# MAIN.net
KiCad netlist of a schematic drawn in Altium Designer
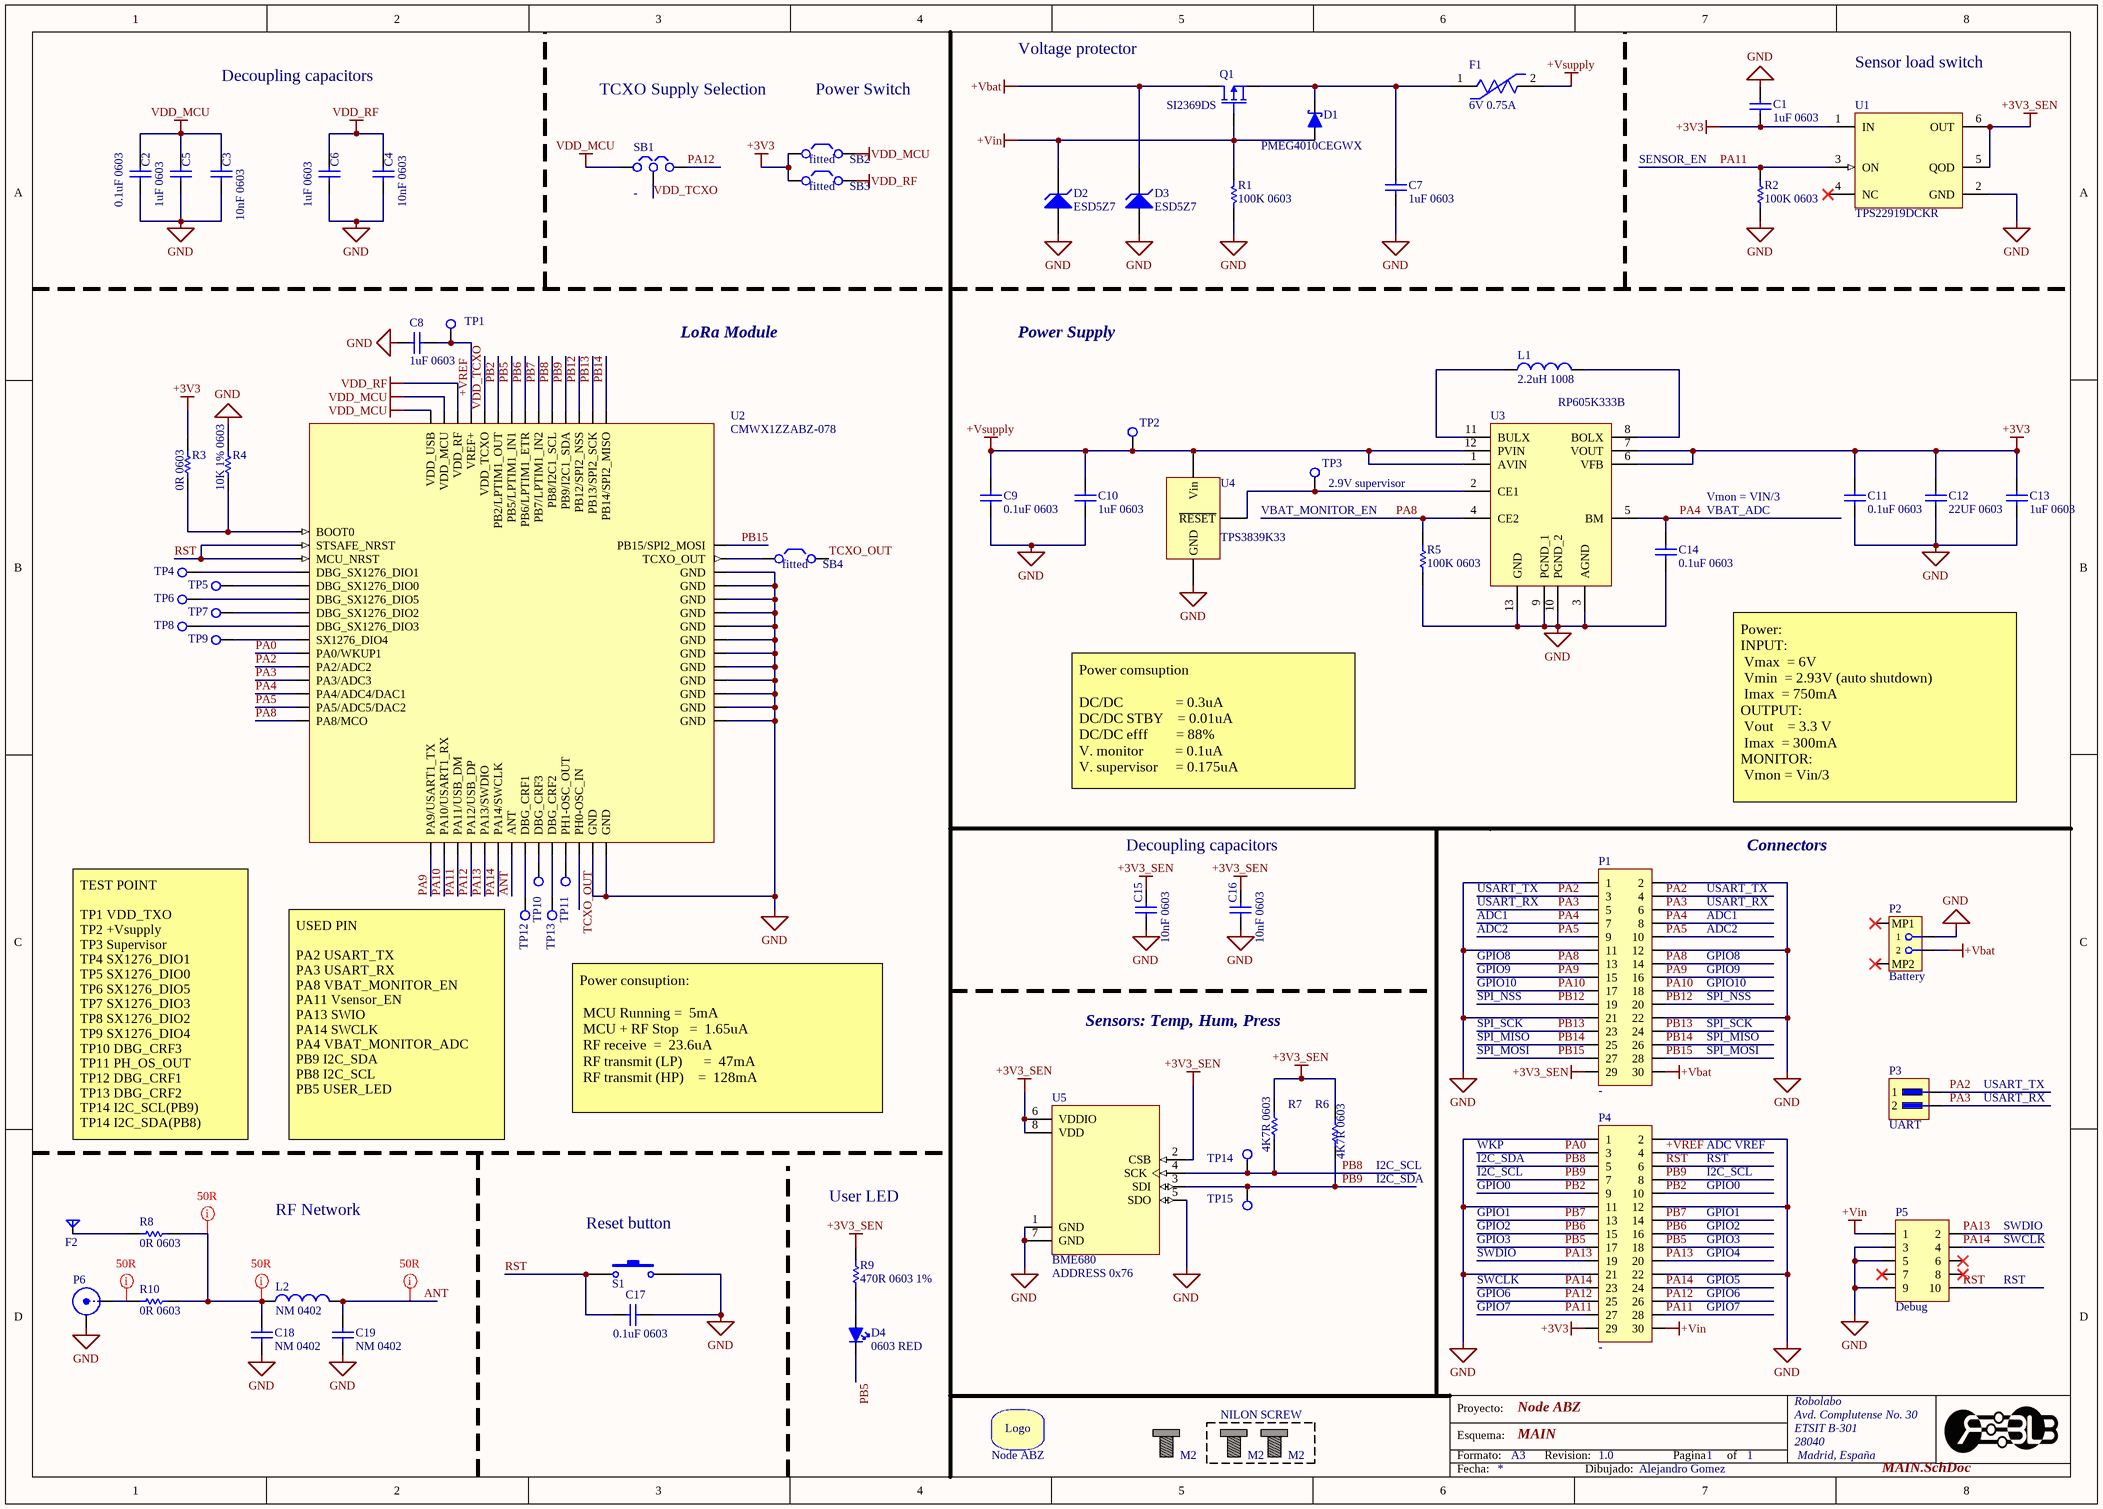
[diagram p0: MAIN.SchDoc]

(export (version "E")
  (design (tool "Eeschema 10.0.6"))
  (components
    (comp (ref "C1")
      (value "1uF 0603")
      (footprint "CAP_SMD_0603")
      (description "CAP CER, 1UF, 10V, X5R, 10%, 0603")
      (fields
        (field (name "MANUFACTURER") "KEMET")
        (field (name "MANUFACTURER PART NUMBER") "C0603C105K8PACTU")
      )
      (libsource (lib "Ceramic_Capacitor") (part "C0603C105K8PACTU"))
    )
    (comp (ref "C2")
      (value "0.1uF 0603")
      (footprint "CAP_SMD_0603")
      (description "Cap Ceramic 0.1uF 6.3V X7R 10% Pad SMD 0603 125°C T/R")
      (fields (field (name "TOLERANCE") "10%"))
      (libsource (lib "Ceramic_Capacitor") (part "C0603C104K9RACTU"))
    )
    (comp (ref "C3")
      (value "10nF 0603")
      (footprint "CAP_SMD_0603")
      (fields
        (field (name "TOLERANCE") "10%")
        (field (name "MANUFACTURER") "KEMET")
        (field (name "MANUFACTURER PART NUMBER") "C0603C103K5RACTU")
      )
      (libsource (lib "Ceramic_Capacitor") (part "C0603C103K5RACTU"))
    )
    (comp (ref "C4")
      (value "10nF 0603")
      (footprint "CAP_SMD_0603")
      (fields
        (field (name "TOLERANCE") "10%")
        (field (name "MANUFACTURER") "KEMET")
        (field (name "MANUFACTURER PART NUMBER") "C0603C103K5RACTU")
      )
      (libsource (lib "Ceramic_Capacitor") (part "C0603C103K5RACTU"))
    )
    (comp (ref "C5")
      (value "1uF 0603")
      (footprint "CAP_SMD_0603")
      (description "CAP CER, 1UF, 10V, X5R, 10%, 0603")
      (fields
        (field (name "MANUFACTURER") "KEMET")
        (field (name "MANUFACTURER PART NUMBER") "C0603C105K8PACTU")
      )
      (libsource (lib "Ceramic_Capacitor") (part "C0603C105K8PACTU"))
    )
    (comp (ref "C6")
      (value "1uF 0603")
      (footprint "CAP_SMD_0603")
      (description "CAP CER, 1UF, 10V, X5R, 10%, 0603")
      (fields
        (field (name "MANUFACTURER") "KEMET")
        (field (name "MANUFACTURER PART NUMBER") "C0603C105K8PACTU")
      )
      (libsource (lib "Ceramic_Capacitor") (part "C0603C105K8PACTU"))
    )
    (comp (ref "C7")
      (value "1uF 0603")
      (footprint "CAP_SMD_0603")
      (description "CAP CER, 1UF, 10V, X5R, 10%, 0603")
      (fields
        (field (name "MANUFACTURER") "KEMET")
        (field (name "MANUFACTURER PART NUMBER") "C0603C105K8PACTU")
      )
      (libsource (lib "Ceramic_Capacitor") (part "C0603C105K8PACTU"))
    )
    (comp (ref "C8")
      (value "1uF 0603")
      (footprint "CAP_SMD_0603")
      (description "CAP CER, 1UF, 10V, X5R, 10%, 0603")
      (fields
        (field (name "MANUFACTURER") "KEMET")
        (field (name "MANUFACTURER PART NUMBER") "C0603C105K8PACTU")
      )
      (libsource (lib "Ceramic_Capacitor") (part "C0603C105K8PACTU"))
    )
    (comp (ref "C9")
      (value "0.1uF 0603")
      (footprint "CAP_SMD_0603")
      (description "CAP CER, 0.1UF, 6.3V, X7R, 10%, 0603")
      (fields (field (name "TOLERANCE") "10%"))
      (libsource (lib "Ceramic_Capacitor") (part "C0603C104K9RACTU"))
    )
    (comp (ref "C10")
      (value "1uF 0603")
      (footprint "CAP_SMD_0603")
      (description "CAP CER, 1UF, 10V, X5R, 10%, 0603")
      (fields
        (field (name "MANUFACTURER") "KEMET")
        (field (name "MANUFACTURER PART NUMBER") "C0603C105K8PACTU")
      )
      (libsource (lib "Ceramic_Capacitor") (part "C0603C105K8PACTU"))
    )
    (comp (ref "C11")
      (value "0.1uF 0603")
      (footprint "CAP_SMD_0603")
      (description "CAP CER, 0.1UF, 6.3V, X7R, 10%, 0603")
      (fields (field (name "TOLERANCE") "10%"))
      (libsource (lib "Ceramic_Capacitor") (part "C0603C104K9RACTU"))
    )
    (comp (ref "C12")
      (value "22UF 0603")
      (footprint "CAP_SMD_0603")
      (description "CAP CER, 22UF, 100V, X8R, 2%, 0603")
      (fields
        (field (name "MANUFACTURER") "KEMET")
        (field (name "MANUFACTURER PART NUMBER") "C0603C300G1HACTU")
      )
      (libsource (lib "Ceramic_Capacitor") (part "C0603C300G1HACTU"))
    )
    (comp (ref "C13")
      (value "1uF 0603")
      (footprint "CAP_SMD_0603")
      (description "CAP CER, 1UF, 10V, X5R, 10%, 0603")
      (fields
        (field (name "MANUFACTURER") "KEMET")
        (field (name "MANUFACTURER PART NUMBER") "C0603C105K8PACTU")
      )
      (libsource (lib "Ceramic_Capacitor") (part "C0603C105K8PACTU"))
    )
    (comp (ref "C14")
      (value "0.1uF 0603")
      (footprint "CAP_SMD_0603")
      (description "CAP CER, 0.1UF, 6.3V, X7R, 10%, 0603")
      (fields (field (name "TOLERANCE") "10%"))
      (libsource (lib "Ceramic_Capacitor") (part "C0603C104K9RACTU"))
    )
    (comp (ref "C15")
      (value "10nF 0603")
      (footprint "CAP_SMD_0603")
      (fields
        (field (name "TOLERANCE") "10%")
        (field (name "MANUFACTURER") "KEMET")
        (field (name "MANUFACTURER PART NUMBER") "C0603C103K5RACTU")
      )
      (libsource (lib "Ceramic_Capacitor") (part "C0603C103K5RACTU"))
    )
    (comp (ref "C16")
      (value "10nF 0603")
      (footprint "CAP_SMD_0603")
      (fields
        (field (name "TOLERANCE") "10%")
        (field (name "MANUFACTURER") "KEMET")
        (field (name "MANUFACTURER PART NUMBER") "C0603C103K5RACTU")
      )
      (libsource (lib "Ceramic_Capacitor") (part "C0603C103K5RACTU"))
    )
    (comp (ref "C17")
      (value "0.1uF 0603")
      (footprint "CAP_SMD_0603")
      (description "Cap Ceramic 0.1uF 6.3V X7R 10% Pad SMD 0603 125°C T/R")
      (fields (field (name "TOLERANCE") "10%"))
      (libsource (lib "Ceramic_Capacitor") (part "C0603C104K9RACTU"))
    )
    (comp (ref "C18")
      (value "NM 0402")
      (footprint "CAP_SMD_0402")
      (description "NM")
      (fields (field (name "TOLERANCE") "10%"))
      (libsource (lib "Ceramic_Capacitor") (part "C0603C103K9RACTU"))
    )
    (comp (ref "C19")
      (value "NM 0402")
      (footprint "CAP_SMD_0402")
      (description "NM")
      (fields (field (name "TOLERANCE") "10%"))
      (libsource (lib "Ceramic_Capacitor") (part "C0603C103K9RACTU"))
    )
    (comp (ref "D1")
      (value "PMEG4010CEGWX")
      (footprint "SODFL358X130-2N")
      (description "DIODE SCHOTTKY 40V 1A 570mV SOD123")
      (fields (field (name "MANUFACTURER") "Nexperia"))
      (libsource (lib "schottky") (part "PMEG4010CEGWX"))
    )
    (comp (ref "D2")
      (value "ESD5Z7")
      (footprint "SODFL160X70-2N")
      (description "TVS Diodes / ESD Suppressors SOD523 ESD DIODE")
      (fields
        (field (name "MANUFACTURER") "ON Semiconductor")
        (field (name "MANUFACTURER PART NUMBER") "ESD5Z7.0T1G")
      )
      (libsource (lib "ESD") (part "ESD5Z7.0T1G"))
    )
    (comp (ref "D3")
      (value "ESD5Z7")
      (footprint "SODFL160X70-2N")
      (description "TVS Diodes / ESD Suppressors SOD523 ESD DIODE")
      (fields
        (field (name "MANUFACTURER") "ON Semiconductor")
        (field (name "MANUFACTURER PART NUMBER") "ESD5Z7.0T1G")
      )
      (libsource (lib "ESD") (part "ESD5Z7.0T1G"))
    )
    (comp (ref "D4")
      (value "0603 RED")
      (footprint "DIODE_LED_SMD_0603")
      (description "Led, Red, 65MCD, 631NM, SMD, 1608")
      (fields
        (field (name "MANUFACTURER") "Kingbright")
        (field (name "MANUFACTURER PART NUMBER") "KPG1-1608SURC-TT")
      )
      (libsource (lib "LED") (part "KPG1-1608SURC-TT"))
    )
    (comp (ref "F1")
      (value "6V 0.75A")
      (footprint "FP-0ZCK0075FF2E-MFG")
      (description "BEL FUSE - 0ZCK0075FF2E - FUSE, RESETTABLE PTC, 6VDC, 0.75A, SMD")
      (fields (field (name "MANUFACTURER") "Bel") (field (name "MANUFACTURER PART NUMBER") "0ZCK0075FF2E"))
      (libsource (lib "PPTC_Fuses") (part "0ZCK0075FF2E"))
    )
    (comp (ref "F2")
      (value "Helical 868-915Mhz")
      (footprint "Helical_868-915MHZ")
      (description "19x11mm Helical antenna. Requieres load matching  (impedance at 868MHz: 10-88j, VSWR 22)")
      (libsource (lib "antenna_pcb") (part "Helical_868-915MHZ"))
    )
    (comp (ref "L1")
      (value "2.2uH 1008")
      (footprint "IND_SMD_1008")
      (description "2.2uH, 1.3A , 20%, 1MHz")
      (fields
        (field (name "MANUFACTURER") "Bourns")
        (field (name "MANUFACTURER PART NUMBER") "CVH252009-2R2M")
      )
      (libsource (lib "Fixed_inductors") (part "CVH252009-2R2M"))
    )
    (comp (ref "L2")
      (value "NM 0402")
      (footprint "IND_SMD_0402")
      (description "NM")
      (fields
        (field (name "MANUFACTURER") "Fair-Rite")
        (field (name "MANUFACTURER PART NUMBER") "2506031217Z0")
      )
      (libsource (lib "Ferrite") (part "2506031217Z0"))
    )
    (comp (ref "logo1")
      (value "Node ABZ")
      (footprint "Robolabo10x25")
      (libsource (lib "logo") (part "Robolabo"))
    )
    (comp (ref "P1")
      (value "-")
      (footprint "CONN-2X15-1.27-MALE-RECT-SMD")
      (description "CONN-2X15-1.27-MALE-RECT")
      (libsource (lib "pin") (part "CONN-2X15-1.27-MALE-RECT"))
    )
    (comp (ref "P2")
      (value "Battery")
      (footprint "JST- S2B-PH-SM4-TB(LF)(SN)-2_V")
      (description "CONN MALE RECT 2 POS 2mm")
      (libsource (lib "PCB_CONNECTOR") (part "S2B-PH-SM4-TB"))
    )
    (comp (ref "P3")
      (value "UART")
      (footprint "CONN-1X2-2.54-PCB")
      (libsource (lib "pin") (part "CONN-1X2-2.54-PCB"))
    )
    (comp (ref "P4")
      (value "-")
      (footprint "CONN-2X15-1.27-MALE-RECT-SMD")
      (description "CONN-2X15-1.27-MALE-RECT")
      (libsource (lib "pin") (part "CONN-2X15-1.27-MALE-RECT"))
    )
    (comp (ref "P5")
      (value "Debug")
      (footprint "CONN-2X5-1.27-PCB")
      (description "CONN-2X5-1.27-MALE-RECT")
      (libsource (lib "pin") (part "CONN-2X5-1.27-MALE-RECT"))
    )
    (comp (ref "P6")
      (value "SMA")
      (footprint "ULFConnector")
      (description "MOLEX   73412-0110   RF COAXIAL, MICROCOAXIAL, JACK, 50OHM")
      (fields (field (name "MANUFACTURER") "Molex") (field (name "MANUFACTURER PART NUMBER") "73412-0110"))
      (libsource (lib "RF_Connectors") (part "73412-0110"))
    )
    (comp (ref "Q1")
      (value "SI2369DS")
      (footprint "SOT95P237X120-3N")
      (description "VISHAY - SI2369DS-T1-GE3 - MOSFET, P-CH, -30V, -7.6A, 150DEG C")
      (fields
        (field (name "MANUFACTURER") "Vishay Siliconix")
        (field (name "MANUFACTURER PART NUMBER") "SI2369DS-T1-GE3")
      )
      (libsource (lib "MOSFET") (part "SI2369DS-T1-GE3"))
    )
    (comp (ref "R1")
      (value "100K 0603")
      (footprint "RES_SMD_0603")
      (description "RES SMD 100K OHM 1% 1/10W 0603")
      (fields
        (field (name "MANUFACTURER") "Vishay")
        (field (name "MANUFACTURER PART NUMBER") "CRCW0603100KFKEAHP")
      )
      (libsource (lib "Resistor") (part "CRCW0603100KFKEAHP"))
    )
    (comp (ref "R2")
      (value "100K 0603")
      (footprint "RES_SMD_0603")
      (description "RES SMD 100K OHM 1% 1/10W 0603")
      (fields
        (field (name "MANUFACTURER") "Vishay")
        (field (name "MANUFACTURER PART NUMBER") "CRCW0603100KFKEAHP")
      )
      (libsource (lib "Resistor") (part "CRCW0603100KFKEAHP"))
    )
    (comp (ref "R3")
      (value "0R 0603")
      (footprint "RES_SMD_0603")
      (description "RES SMD 0 OHM 0603")
      (fields (field (name "TOLERANCE") "5%"))
      (libsource (lib "Resistor") (part "CRCW0603-0000Z0EA"))
    )
    (comp (ref "R4")
      (value "10K 1% 0603")
      (footprint "RES_SMD_0603")
      (description "RES SMD 10K OHM 1% 1/10W 0603")
      (fields (field (name "TOLERANCE") "1%") (field (name "MANUFACTURER") "Vishay"))
      (libsource (lib "Resistor") (part "CRCW060310K0FKEA"))
    )
    (comp (ref "R5")
      (value "100K 0603")
      (footprint "RES_SMD_0603")
      (description "RES SMD 100K OHM 1% 1/10W 0603")
      (fields
        (field (name "MANUFACTURER") "Vishay")
        (field (name "MANUFACTURER PART NUMBER") "CRCW0603100KFKEAHP")
      )
      (libsource (lib "Resistor") (part "CRCW0603100KFKEAHP"))
    )
    (comp (ref "R6")
      (value "4K7R 0603")
      (footprint "RES_SMD_0603")
      (description "RES SMD 4.7K OHM 1% 1/10W 0603")
      (fields (field (name "TOLERANCE") "1%"))
      (libsource (lib "Resistor") (part "CRCW06034K70FKTA"))
    )
    (comp (ref "R7")
      (value "4K7R 0603")
      (footprint "RES_SMD_0603")
      (description "RES SMD 4.7K OHM 1% 1/10W 0603")
      (fields (field (name "TOLERANCE") "1%"))
      (libsource (lib "Resistor") (part "CRCW06034K70FKTA"))
    )
    (comp (ref "R8")
      (value "0R 0603")
      (footprint "RED_SMD_0402")
      (description "RES SMD 0 OHM 0603")
      (fields (field (name "TOLERANCE") "5%"))
      (libsource (lib "Resistor") (part "CRCW0603-0000Z0EA"))
    )
    (comp (ref "R9")
      (value "470R 0603 1%")
      (footprint "RES_SMD_0603")
      (description "RES SMD 470 OHM 1% 1/10W 0603")
      (fields (field (name "TOLERANCE") "1%") (field (name "MANUFACTURER") "Vishay"))
      (libsource (lib "Resistor") (part "CRCW0603470RFKEAHP"))
    )
    (comp (ref "R10")
      (value "0R 0603")
      (footprint "RED_SMD_0402")
      (description "RES SMD 0 OHM 0603")
      (fields (field (name "TOLERANCE") "5%"))
      (libsource (lib "Resistor") (part "CRCW0603-0000Z0EA"))
    )
    (comp (ref "S1")
      (value "SPST 4.6x2.8mm")
      (footprint "KMR4_CK_SWITCH")
      (fields (field (name "MANUFACTURER") "ITT C&K") (field (name "MANUFACTURER PART NUMBER") "KMR441NGLFS"))
      (libsource (lib "switch") (part "KMR441NGLFS"))
    )
    (comp (ref "SB1")
      (value "-")
      (footprint "0603_SB_3P")
      (description "Solder Bridge smd")
      (libsource (lib "solder_brige") (part "SB_3P"))
    )
    (comp (ref "SB2")
      (value "fitted")
      (footprint "0603_SB_2P")
      (description "Solder Bridge smd")
      (libsource (lib "solder_brige") (part "SB_2P"))
    )
    (comp (ref "SB3")
      (value "fitted")
      (footprint "0603_SB_2P")
      (description "Solder Bridge smd")
      (libsource (lib "solder_brige") (part "SB_2P"))
    )
    (comp (ref "SB4")
      (value "fitted")
      (footprint "0603_SB_2P")
      (description "Solder Bridge smd")
      (libsource (lib "solder_brige") (part "SB_2P"))
    )
    (comp (ref "screw1") (value "M2") (footprint "M2") (libsource (lib "screw") (part "screw_M2")))
    (comp (ref "screw2") (value "M2") (footprint "M2_NOPAD") (libsource (lib "screw") (part "screw_M2")))
    (comp (ref "screw3") (value "M2") (footprint "M2_NOPAD") (libsource (lib "screw") (part "screw_M2")))
    (comp (ref "TP1") (value "-") (footprint "TP_1MM") (libsource (lib "test_point") (part "TP SMD")))
    (comp (ref "TP2") (value "-") (footprint "TP_1MM") (libsource (lib "test_point") (part "TP SMD")))
    (comp (ref "TP3") (value "-") (footprint "TP_1MM") (libsource (lib "test_point") (part "TP SMD")))
    (comp (ref "TP4") (value "-") (footprint "TP_1MM") (libsource (lib "test_point") (part "TP SMD")))
    (comp (ref "TP5") (value "-") (footprint "TP_1MM") (libsource (lib "test_point") (part "TP SMD")))
    (comp (ref "TP6") (value "-") (footprint "TP_1MM") (libsource (lib "test_point") (part "TP SMD")))
    (comp (ref "TP7") (value "-") (footprint "TP_1MM") (libsource (lib "test_point") (part "TP SMD")))
    (comp (ref "TP8") (value "-") (footprint "TP_1MM") (libsource (lib "test_point") (part "TP SMD")))
    (comp (ref "TP9") (value "-") (footprint "TP_1MM") (libsource (lib "test_point") (part "TP SMD")))
    (comp (ref "TP10") (value "-") (footprint "TP_1MM") (libsource (lib "test_point") (part "TP SMD")))
    (comp (ref "TP11") (value "-") (footprint "TP_1MM") (libsource (lib "test_point") (part "TP SMD")))
    (comp (ref "TP12") (value "-") (footprint "TP_1MM") (libsource (lib "test_point") (part "TP SMD")))
    (comp (ref "TP13") (value "-") (footprint "TP_1MM") (libsource (lib "test_point") (part "TP SMD")))
    (comp (ref "TP14") (value "-") (footprint "TP_1MM") (libsource (lib "test_point") (part "TP SMD")))
    (comp (ref "TP15") (value "-") (footprint "TP_1MM") (libsource (lib "test_point") (part "TP SMD")))
    (comp (ref "U1")
      (value "TPS22919DCKR")
      (footprint "FP-DCK0006A-IPC_B")
      (description "5.5-V, 1.5-A, 90-mΩ load switch with adj. output discharge 6-SC70 -40 to 105")
      (fields (field (name "MANUFACTURER") "Texas Instruments"))
      (libsource (lib "load_switch") (part "TPS22919DCKR"))
    )
    (comp (ref "U2")
      (value "CMWX1ZZABZ-078")
      (footprint "XCVR_CMWX1ZZABZ-078")
      (description "LORA MODULE")
      (libsource (lib "mcu") (part "CMWX1ZZABZ-078"))
    )
    (comp (ref "U3")
      (value "RP605K333B")
      (footprint "SON50P270X300X60-13N")
      (fields (field (name "MANUFACTURER") "Ricoh") (field (name "MANUFACTURER PART NUMBER") "RP605K333B-TR"))
      (libsource (lib "Switching_VR") (part "RP605K333B-TR"))
    )
    (comp (ref "U4")
      (value "TPS3839K33")
      (footprint "SOT95P237X120-3N")
      (description "IC LP SUPERVISRY CIRCUIT SOT23-3")
      (fields
        (field (name "MANUFACTURER") "Texas Instruments")
        (field (name "MANUFACTURER PART NUMBER") "TPS3839K33DBZR")
      )
      (libsource (lib "circuit_supervisor") (part "TPS3839K33DBZR"))
    )
    (comp (ref "U5")
      (value "BME680")
      (footprint "PSON80P300X300X100-8N")
      (description "Pressure, Temperature and Humidity Sensor Digital Output 1.8V 8-Pin LGA")
      (fields (field (name "MANUFACTURER") "Bosch Sensortec"))
      (libsource (lib "Temperature_Sensors") (part "BME680"))
    )
  )
  (nets
    (net (code "1") (name "+3V3") (class "Default")
      (node (ref "C1") (pin "2") (pinfunction "2_2") (pintype "passive"))
      (node (ref "C11") (pin "2") (pinfunction "2_2") (pintype "passive"))
      (node (ref "C12") (pin "2") (pinfunction "2_2") (pintype "passive"))
      (node (ref "C13") (pin "2") (pinfunction "2_2") (pintype "passive"))
      (node (ref "P4") (pin "29") (pinfunction "29_29") (pintype "passive"))
      (node (ref "R3") (pin "2") (pinfunction "2_2") (pintype "passive"))
      (node (ref "SB2") (pin "1") (pinfunction "C1_1") (pintype "passive"))
      (node (ref "SB3") (pin "1") (pinfunction "C1_1") (pintype "passive"))
      (node (ref "U1") (pin "1") (pinfunction "IN_1") (pintype "power_in"))
      (node (ref "U3") (pin "6") (pinfunction "VFB_6") (pintype "passive"))
      (node (ref "U3") (pin "7") (pinfunction "VOUT_7") (pintype "passive"))
    )
    (net (code "2") (name "+3V3_SEN") (class "Default")
      (node (ref "C15") (pin "2") (pinfunction "2_2") (pintype "passive"))
      (node (ref "C16") (pin "2") (pinfunction "2_2") (pintype "passive"))
      (node (ref "P1") (pin "29") (pinfunction "29_29") (pintype "passive"))
      (node (ref "R6") (pin "2") (pinfunction "2_2") (pintype "passive"))
      (node (ref "R7") (pin "2") (pinfunction "2_2") (pintype "passive"))
      (node (ref "R9") (pin "2") (pinfunction "2_2") (pintype "passive"))
      (node (ref "U1") (pin "5") (pinfunction "QOD_5") (pintype "passive"))
      (node (ref "U1") (pin "6") (pinfunction "OUT_6") (pintype "power_in"))
      (node (ref "U5") (pin "2") (pinfunction "CSB_2") (pintype "input"))
      (node (ref "U5") (pin "6") (pinfunction "VDDIO_6") (pintype "power_in"))
      (node (ref "U5") (pin "8") (pinfunction "VDD_8") (pintype "power_in"))
    )
    (net (code "3") (name "+Vbat") (class "Default")
      (node (ref "D3") (pin "2") (pinfunction "K_2") (pintype "passive"))
      (node (ref "P1") (pin "30") (pinfunction "30_30") (pintype "passive"))
      (node (ref "P2") (pin "2") (pinfunction "2_2") (pintype "passive"))
      (node (ref "Q1") (pin "3") (pinfunction "D_3") (pintype "passive"))
    )
    (net (code "4") (name "+Vin") (class "Default")
      (node (ref "D1") (pin "1") (pinfunction "A_1") (pintype "passive"))
      (node (ref "D2") (pin "2") (pinfunction "K_2") (pintype "passive"))
      (node (ref "P4") (pin "30") (pinfunction "30_30") (pintype "passive"))
      (node (ref "P5") (pin "1") (pinfunction "1_1") (pintype "passive"))
      (node (ref "Q1") (pin "1") (pinfunction "G_1") (pintype "passive"))
      (node (ref "R1") (pin "1") (pinfunction "1_1") (pintype "passive"))
    )
    (net (code "5") (name "+Vsupply") (class "Default")
      (node (ref "C10") (pin "2") (pinfunction "2_2") (pintype "passive"))
      (node (ref "C9") (pin "2") (pinfunction "2_2") (pintype "passive"))
      (node (ref "F1") (pin "2") (pinfunction "2_2") (pintype "passive"))
      (node (ref "TP2") (pin "1") (pinfunction "-_1") (pintype "passive"))
      (node (ref "U3") (pin "1") (pinfunction "AVIN_1") (pintype "passive"))
      (node (ref "U3") (pin "12") (pinfunction "PVIN_12") (pintype "passive"))
      (node (ref "U4") (pin "3") (pinfunction "Vin_3") (pintype "passive"))
    )
    (net (code "6") (name "/+VREF") (class "Default")
      (node (ref "C8") (pin "1") (pinfunction "1_1") (pintype "passive"))
      (node (ref "P4") (pin "4") (pinfunction "4_4") (pintype "passive"))
      (node (ref "TP1") (pin "1") (pinfunction "-_1") (pintype "passive"))
      (node (ref "U2") (pin "32") (pinfunction "VREF+_32") (pintype "power_in"))
    )
    (net (code "7") (name "/ANT") (class "Default")
      (node (ref "C19") (pin "2") (pinfunction "2_2") (pintype "passive"))
      (node (ref "L2") (pin "2") (pinfunction "2_2") (pintype "passive"))
      (node (ref "U2") (pin "26") (pinfunction "ANT_26") (pintype "bidirectional"))
    )
    (net (code "8") (name "/PA0") (class "Default")
      (node (ref "P4") (pin "3") (pinfunction "3_3") (pintype "passive"))
      (node (ref "U2") (pin "33") (pinfunction "PA0/WKUP1_33") (pintype "bidirectional"))
    )
    (net (code "9") (name "/PA2") (class "Default")
      (node (ref "P1") (pin "3") (pinfunction "3_3") (pintype "passive"))
      (node (ref "P1") (pin "4") (pinfunction "4_4") (pintype "passive"))
      (node (ref "P3") (pin "1") (pinfunction "1_1") (pintype "passive"))
      (node (ref "U2") (pin "24") (pinfunction "PA2/ADC2_24") (pintype "bidirectional"))
    )
    (net (code "10") (name "/PA3") (class "Default")
      (node (ref "P1") (pin "5") (pinfunction "5_5") (pintype "passive"))
      (node (ref "P1") (pin "6") (pinfunction "6_6") (pintype "passive"))
      (node (ref "P3") (pin "2") (pinfunction "2_2") (pintype "passive"))
      (node (ref "U2") (pin "23") (pinfunction "PA3/ADC3_23") (pintype "bidirectional"))
    )
    (net (code "11") (name "/PA4") (class "Default")
      (node (ref "C14") (pin "2") (pinfunction "2_2") (pintype "passive"))
      (node (ref "P1") (pin "7") (pinfunction "7_7") (pintype "passive"))
      (node (ref "P1") (pin "8") (pinfunction "8_8") (pintype "passive"))
      (node (ref "U2") (pin "22") (pinfunction "PA4/ADC4/DAC1_22") (pintype "bidirectional"))
      (node (ref "U3") (pin "5") (pinfunction "BM_5") (pintype "passive"))
    )
    (net (code "12") (name "/PA5") (class "Default")
      (node (ref "P1") (pin "10") (pinfunction "10_10") (pintype "passive"))
      (node (ref "P1") (pin "9") (pinfunction "9_9") (pintype "passive"))
      (node (ref "U2") (pin "21") (pinfunction "PA5/ADC5/DAC2_21") (pintype "bidirectional"))
    )
    (net (code "13") (name "/PA8") (class "Default")
      (node (ref "P1") (pin "13") (pinfunction "13_13") (pintype "passive"))
      (node (ref "P1") (pin "14") (pinfunction "14_14") (pintype "passive"))
      (node (ref "R5") (pin "2") (pinfunction "2_2") (pintype "passive"))
      (node (ref "U2") (pin "20") (pinfunction "PA8/MCO_20") (pintype "bidirectional"))
      (node (ref "U3") (pin "4") (pinfunction "CE2_4") (pintype "passive"))
    )
    (net (code "14") (name "/PA9") (class "Default")
      (node (ref "P1") (pin "15") (pinfunction "15_15") (pintype "passive"))
      (node (ref "P1") (pin "16") (pinfunction "16_16") (pintype "passive"))
      (node (ref "U2") (pin "19") (pinfunction "PA9/USART1_TX_19") (pintype "bidirectional"))
    )
    (net (code "15") (name "/PA10") (class "Default")
      (node (ref "P1") (pin "17") (pinfunction "17_17") (pintype "passive"))
      (node (ref "P1") (pin "18") (pinfunction "18_18") (pintype "passive"))
      (node (ref "U2") (pin "18") (pinfunction "PA10/USART1_RX_18") (pintype "bidirectional"))
    )
    (net (code "16") (name "/PA11") (class "Default")
      (node (ref "P4") (pin "27") (pinfunction "27_27") (pintype "passive"))
      (node (ref "P4") (pin "28") (pinfunction "28_28") (pintype "passive"))
      (node (ref "R2") (pin "2") (pinfunction "2_2") (pintype "passive"))
      (node (ref "U1") (pin "3") (pinfunction "ON_3") (pintype "input"))
      (node (ref "U2") (pin "2") (pinfunction "PA11/USB_DM_2") (pintype "bidirectional"))
    )
    (net (code "17") (name "/PA12") (class "Default")
      (node (ref "P4") (pin "25") (pinfunction "25_25") (pintype "passive"))
      (node (ref "P4") (pin "26") (pinfunction "26_26") (pintype "passive"))
      (node (ref "SB1") (pin "3") (pinfunction "C2_3") (pintype "passive"))
      (node (ref "U2") (pin "1") (pinfunction "PA12/USB_DP_1") (pintype "bidirectional"))
    )
    (net (code "18") (name "/PA13") (class "Default")
      (node (ref "P4") (pin "19") (pinfunction "19_19") (pintype "passive"))
      (node (ref "P4") (pin "20") (pinfunction "20_20") (pintype "passive"))
      (node (ref "P5") (pin "2") (pinfunction "2_2") (pintype "passive"))
      (node (ref "U2") (pin "41") (pinfunction "PA13/SWDIO_41") (pintype "bidirectional"))
    )
    (net (code "19") (name "/PA14") (class "Default")
      (node (ref "P4") (pin "23") (pinfunction "23_23") (pintype "passive"))
      (node (ref "P4") (pin "24") (pinfunction "24_24") (pintype "passive"))
      (node (ref "P5") (pin "4") (pinfunction "4_4") (pintype "passive"))
      (node (ref "U2") (pin "42") (pinfunction "PA14/SWCLK_42") (pintype "bidirectional"))
    )
    (net (code "20") (name "/PB2") (class "Default")
      (node (ref "P4") (pin "10") (pinfunction "10_10") (pintype "passive"))
      (node (ref "P4") (pin "9") (pinfunction "9_9") (pintype "passive"))
      (node (ref "U2") (pin "37") (pinfunction "PB2/LPTIM1_OUT_37") (pintype "bidirectional"))
    )
    (net (code "21") (name "/PB5") (class "Default")
      (node (ref "D4") (pin "2") (pinfunction "K_2") (pintype "passive"))
      (node (ref "P4") (pin "17") (pinfunction "17_17") (pintype "passive"))
      (node (ref "P4") (pin "18") (pinfunction "18_18") (pintype "passive"))
      (node (ref "U2") (pin "40") (pinfunction "PB5/LPTIM1_IN1_40") (pintype "bidirectional"))
    )
    (net (code "22") (name "/PB6") (class "Default")
      (node (ref "P4") (pin "15") (pinfunction "15_15") (pintype "passive"))
      (node (ref "P4") (pin "16") (pinfunction "16_16") (pintype "passive"))
      (node (ref "U2") (pin "39") (pinfunction "PB6/LPTIM1_ETR_39") (pintype "bidirectional"))
    )
    (net (code "23") (name "/PB7") (class "Default")
      (node (ref "P4") (pin "13") (pinfunction "13_13") (pintype "passive"))
      (node (ref "P4") (pin "14") (pinfunction "14_14") (pintype "passive"))
      (node (ref "U2") (pin "38") (pinfunction "PB7/LPTIM1_IN2_38") (pintype "bidirectional"))
    )
    (net (code "24") (name "/PB8") (class "Default")
      (node (ref "P4") (pin "5") (pinfunction "5_5") (pintype "passive"))
      (node (ref "R7") (pin "1") (pinfunction "1_1") (pintype "passive"))
      (node (ref "TP14") (pin "1") (pinfunction "-_1") (pintype "passive"))
      (node (ref "U2") (pin "35") (pinfunction "PB8/I2C1_SCL_35") (pintype "bidirectional"))
      (node (ref "U5") (pin "4") (pinfunction "SCK_4") (pintype "input"))
    )
    (net (code "25") (name "/PB9") (class "Default")
      (node (ref "P4") (pin "7") (pinfunction "7_7") (pintype "passive"))
      (node (ref "P4") (pin "8") (pinfunction "8_8") (pintype "passive"))
      (node (ref "R6") (pin "1") (pinfunction "1_1") (pintype "passive"))
      (node (ref "TP15") (pin "1") (pinfunction "-_1") (pintype "passive"))
      (node (ref "U2") (pin "36") (pinfunction "PB9/I2C1_SDA_36") (pintype "bidirectional"))
      (node (ref "U5") (pin "3") (pinfunction "SDI_3") (pintype "bidirectional"))
    )
    (net (code "26") (name "/PB12") (class "Default")
      (node (ref "P1") (pin "19") (pinfunction "19_19") (pintype "passive"))
      (node (ref "P1") (pin "20") (pinfunction "20_20") (pintype "passive"))
      (node (ref "U2") (pin "17") (pinfunction "PB12/SPI2_NSS_17") (pintype "bidirectional"))
    )
    (net (code "27") (name "/PB13") (class "Default")
      (node (ref "P1") (pin "23") (pinfunction "23_23") (pintype "passive"))
      (node (ref "P1") (pin "24") (pinfunction "24_24") (pintype "passive"))
      (node (ref "U2") (pin "16") (pinfunction "PB13/SPI2_SCK_16") (pintype "bidirectional"))
    )
    (net (code "28") (name "/PB14") (class "Default")
      (node (ref "P1") (pin "25") (pinfunction "25_25") (pintype "passive"))
      (node (ref "P1") (pin "26") (pinfunction "26_26") (pintype "passive"))
      (node (ref "U2") (pin "15") (pinfunction "PB14/SPI2_MISO_15") (pintype "bidirectional"))
    )
    (net (code "29") (name "/PB15") (class "Default")
      (node (ref "P1") (pin "27") (pinfunction "27_27") (pintype "passive"))
      (node (ref "P1") (pin "28") (pinfunction "28_28") (pintype "passive"))
      (node (ref "U2") (pin "14") (pinfunction "PB15/SPI2_MOSI_14") (pintype "bidirectional"))
    )
    (net (code "30") (name "/RST") (class "Default")
      (node (ref "C17") (pin "1") (pinfunction "1_1") (pintype "passive"))
      (node (ref "P4") (pin "6") (pinfunction "6_6") (pintype "passive"))
      (node (ref "P5") (pin "10") (pinfunction "10_10") (pintype "passive"))
      (node (ref "S1") (pin "1") (pinfunction "1_1") (pintype "passive"))
      (node (ref "U2") (pin "31") (pinfunction "STSAFE_NRST_31") (pintype "input"))
      (node (ref "U2") (pin "34") (pinfunction "MCU_NRST_34") (pintype "input"))
    )
    (net (code "31") (name "/TCXO_OUT") (class "Default")
      (node (ref "SB4") (pin "2") (pinfunction "C2_2") (pintype "passive"))
      (node (ref "U2") (pin "46") (pinfunction "PH0-OSC_IN_46") (pintype "bidirectional"))
    )
    (net (code "32") (name "/VDD_TCXO") (class "Default")
      (node (ref "SB1") (pin "2") (pinfunction "C2_2") (pintype "passive"))
      (node (ref "U2") (pin "48") (pinfunction "VDD_TCXO_48") (pintype "power_in"))
    )
    (net (code "33") (name "GND") (class "Default")
      (node (ref "C1") (pin "1") (pinfunction "1_1") (pintype "passive"))
      (node (ref "C10") (pin "1") (pinfunction "1_1") (pintype "passive"))
      (node (ref "C11") (pin "1") (pinfunction "1_1") (pintype "passive"))
      (node (ref "C12") (pin "1") (pinfunction "1_1") (pintype "passive"))
      (node (ref "C13") (pin "1") (pinfunction "1_1") (pintype "passive"))
      (node (ref "C14") (pin "1") (pinfunction "1_1") (pintype "passive"))
      (node (ref "C15") (pin "1") (pinfunction "1_1") (pintype "passive"))
      (node (ref "C16") (pin "1") (pinfunction "1_1") (pintype "passive"))
      (node (ref "C17") (pin "2") (pinfunction "2_2") (pintype "passive"))
      (node (ref "C18") (pin "1") (pinfunction "1_1") (pintype "passive"))
      (node (ref "C19") (pin "1") (pinfunction "1_1") (pintype "passive"))
      (node (ref "C2") (pin "1") (pinfunction "1_1") (pintype "passive"))
      (node (ref "C3") (pin "1") (pinfunction "1_1") (pintype "passive"))
      (node (ref "C4") (pin "1") (pinfunction "1_1") (pintype "passive"))
      (node (ref "C5") (pin "1") (pinfunction "1_1") (pintype "passive"))
      (node (ref "C6") (pin "1") (pinfunction "1_1") (pintype "passive"))
      (node (ref "C7") (pin "1") (pinfunction "1_1") (pintype "passive"))
      (node (ref "C8") (pin "2") (pinfunction "2_2") (pintype "passive"))
      (node (ref "C9") (pin "1") (pinfunction "1_1") (pintype "passive"))
      (node (ref "D2") (pin "1") (pinfunction "A_1") (pintype "passive"))
      (node (ref "D3") (pin "1") (pinfunction "A_1") (pintype "passive"))
      (node (ref "P1") (pin "1") (pinfunction "1_1") (pintype "passive"))
      (node (ref "P1") (pin "11") (pinfunction "11_11") (pintype "passive"))
      (node (ref "P1") (pin "12") (pinfunction "12_12") (pintype "passive"))
      (node (ref "P1") (pin "2") (pinfunction "2_2") (pintype "passive"))
      (node (ref "P1") (pin "21") (pinfunction "21_21") (pintype "passive"))
      (node (ref "P1") (pin "22") (pinfunction "22_22") (pintype "passive"))
      (node (ref "P2") (pin "1") (pinfunction "1_1") (pintype "passive"))
      (node (ref "P4") (pin "1") (pinfunction "1_1") (pintype "passive"))
      (node (ref "P4") (pin "11") (pinfunction "11_11") (pintype "passive"))
      (node (ref "P4") (pin "12") (pinfunction "12_12") (pintype "passive"))
      (node (ref "P4") (pin "2") (pinfunction "2_2") (pintype "passive"))
      (node (ref "P4") (pin "21") (pinfunction "21_21") (pintype "passive"))
      (node (ref "P4") (pin "22") (pinfunction "22_22") (pintype "passive"))
      (node (ref "P5") (pin "3") (pinfunction "3_3") (pintype "passive"))
      (node (ref "P5") (pin "5") (pinfunction "5_5") (pintype "passive"))
      (node (ref "P5") (pin "9") (pinfunction "9_9") (pintype "passive"))
      (node (ref "P6") (pin "2") (pinfunction "Y_2") (pintype "passive"))
      (node (ref "R1") (pin "2") (pinfunction "2_2") (pintype "passive"))
      (node (ref "R2") (pin "1") (pinfunction "1_1") (pintype "passive"))
      (node (ref "R4") (pin "2") (pinfunction "2_2") (pintype "passive"))
      (node (ref "R5") (pin "1") (pinfunction "1_1") (pintype "passive"))
      (node (ref "S1") (pin "2") (pinfunction "2_2") (pintype "passive"))
      (node (ref "U1") (pin "2") (pinfunction "GND_2") (pintype "power_in"))
      (node (ref "U2") (pin "25") (pinfunction "GND_25") (pintype "power_in"))
      (node (ref "U2") (pin "27") (pinfunction "GND_27") (pintype "power_in"))
      (node (ref "U2") (pin "3") (pinfunction "GND_3") (pintype "power_in"))
      (node (ref "U2") (pin "44") (pinfunction "GND_44") (pintype "power_in"))
      (node (ref "U2") (pin "49") (pinfunction "GND_49") (pintype "power_in"))
      (node (ref "U2") (pin "50") (pinfunction "GND_50") (pintype "power_in"))
      (node (ref "U2") (pin "51") (pinfunction "GND_51") (pintype "power_in"))
      (node (ref "U2") (pin "52") (pinfunction "GND_52") (pintype "power_in"))
      (node (ref "U2") (pin "53") (pinfunction "GND_53") (pintype "power_in"))
      (node (ref "U2") (pin "54") (pinfunction "GND_54") (pintype "power_in"))
      (node (ref "U2") (pin "55") (pinfunction "GND_55") (pintype "power_in"))
      (node (ref "U2") (pin "56") (pinfunction "GND_56") (pintype "power_in"))
      (node (ref "U2") (pin "57") (pinfunction "GND_57") (pintype "power_in"))
      (node (ref "U2") (pin "7") (pinfunction "GND_7") (pintype "power_in"))
      (node (ref "U3") (pin "10") (pinfunction "PGND_2_10") (pintype "passive"))
      (node (ref "U3") (pin "13") (pinfunction "GND_13") (pintype "passive"))
      (node (ref "U3") (pin "3") (pinfunction "AGND_3") (pintype "passive"))
      (node (ref "U3") (pin "9") (pinfunction "PGND_1_9") (pintype "passive"))
      (node (ref "U4") (pin "1") (pinfunction "GND_1") (pintype "passive"))
      (node (ref "U5") (pin "1") (pinfunction "GND_1") (pintype "power_in"))
      (node (ref "U5") (pin "5") (pinfunction "SDO_5") (pintype "bidirectional"))
      (node (ref "U5") (pin "7") (pinfunction "GND_7") (pintype "power_in"))
    )
    (net (code "34") (name "Net-(C18-Pad2)") (class "Default")
      (node (ref "C18") (pin "2") (pinfunction "2_2") (pintype "passive"))
      (node (ref "L2") (pin "1") (pinfunction "1_1") (pintype "passive"))
      (node (ref "R10") (pin "2") (pinfunction "2_2") (pintype "passive"))
      (node (ref "R8") (pin "2") (pinfunction "2_2") (pintype "passive"))
    )
    (net (code "35") (name "Net-(D1-K)") (class "Default")
      (node (ref "C7") (pin "2") (pinfunction "2_2") (pintype "passive"))
      (node (ref "D1") (pin "2") (pinfunction "K_2") (pintype "passive"))
      (node (ref "F1") (pin "1") (pinfunction "1_1") (pintype "passive"))
      (node (ref "Q1") (pin "2") (pinfunction "S_2") (pintype "passive"))
    )
    (net (code "36") (name "Net-(D4-A)") (class "Default")
      (node (ref "D4") (pin "1") (pinfunction "A_1") (pintype "passive"))
      (node (ref "R9") (pin "1") (pinfunction "1_1") (pintype "passive"))
    )
    (net (code "37") (name "Net-(F2-Pad1)") (class "Default")
      (node (ref "F2") (pin "1") (pinfunction "1_1") (pintype "passive"))
      (node (ref "R8") (pin "1") (pinfunction "1_1") (pintype "passive"))
    )
    (net (code "38") (name "Net-(P6-X)") (class "Default")
      (node (ref "P6") (pin "1") (pinfunction "X_1") (pintype "passive"))
      (node (ref "R10") (pin "1") (pinfunction "1_1") (pintype "passive"))
    )
    (net (code "39") (name "Net-(SB4-C1)") (class "Default")
      (node (ref "SB4") (pin "1") (pinfunction "C1_1") (pintype "passive"))
      (node (ref "U2") (pin "47") (pinfunction "TCXO_OUT_47") (pintype "output"))
    )
    (net (code "40") (name "Net-(TP3--)") (class "Default")
      (node (ref "TP3") (pin "1") (pinfunction "-_1") (pintype "passive"))
      (node (ref "U3") (pin "2") (pinfunction "CE1_2") (pintype "passive"))
      (node (ref "U4") (pin "2") (pinfunction "~{RESET}_2") (pintype "passive"))
    )
    (net (code "41") (name "Net-(TP4--)") (class "Default")
      (node (ref "TP4") (pin "1") (pinfunction "-_1") (pintype "passive"))
      (node (ref "U2") (pin "12") (pinfunction "DBG_SX1276_DIO1_12") (pintype "bidirectional"))
    )
    (net (code "42") (name "Net-(TP5--)") (class "Default")
      (node (ref "TP5") (pin "1") (pinfunction "-_1") (pintype "passive"))
      (node (ref "U2") (pin "13") (pinfunction "DBG_SX1276_DIO0_13") (pintype "bidirectional"))
    )
    (net (code "43") (name "Net-(TP6--)") (class "Default")
      (node (ref "TP6") (pin "1") (pinfunction "-_1") (pintype "passive"))
      (node (ref "U2") (pin "11") (pinfunction "DBG_SX1276_DIO5_11") (pintype "bidirectional"))
    )
    (net (code "44") (name "Net-(TP7--)") (class "Default")
      (node (ref "TP7") (pin "1") (pinfunction "-_1") (pintype "passive"))
      (node (ref "U2") (pin "8") (pinfunction "DBG_SX1276_DIO2_8") (pintype "bidirectional"))
    )
    (net (code "45") (name "Net-(TP8--)") (class "Default")
      (node (ref "TP8") (pin "1") (pinfunction "-_1") (pintype "passive"))
      (node (ref "U2") (pin "9") (pinfunction "DBG_SX1276_DIO3_9") (pintype "bidirectional"))
    )
    (net (code "46") (name "Net-(TP9--)") (class "Default")
      (node (ref "TP9") (pin "1") (pinfunction "-_1") (pintype "passive"))
      (node (ref "U2") (pin "10") (pinfunction "SX1276_DIO4_10") (pintype "bidirectional"))
    )
    (net (code "47") (name "Net-(TP10--)") (class "Default")
      (node (ref "TP10") (pin "1") (pinfunction "-_1") (pintype "passive"))
      (node (ref "U2") (pin "29") (pinfunction "DBG_CRF3_29") (pintype "bidirectional"))
    )
    (net (code "48") (name "Net-(TP11--)") (class "Default")
      (node (ref "TP11") (pin "1") (pinfunction "-_1") (pintype "passive"))
      (node (ref "U2") (pin "45") (pinfunction "PH1-OSC_OUT_45") (pintype "bidirectional"))
    )
    (net (code "49") (name "Net-(TP12--)") (class "Default")
      (node (ref "TP12") (pin "1") (pinfunction "-_1") (pintype "passive"))
      (node (ref "U2") (pin "28") (pinfunction "DBG_CRF1_28") (pintype "bidirectional"))
    )
    (net (code "50") (name "Net-(TP13--)") (class "Default")
      (node (ref "TP13") (pin "1") (pinfunction "-_1") (pintype "passive"))
      (node (ref "U2") (pin "30") (pinfunction "DBG_CRF2_30") (pintype "bidirectional"))
    )
    (net (code "51") (name "Net-(U2-BOOT0)") (class "Default")
      (node (ref "R3") (pin "1") (pinfunction "1_1") (pintype "passive"))
      (node (ref "R4") (pin "1") (pinfunction "1_1") (pintype "passive"))
      (node (ref "U2") (pin "43") (pinfunction "BOOT0_43") (pintype "input"))
    )
    (net (code "52") (name "Net-(U3-BOLX)") (class "Default")
      (node (ref "L1") (pin "2") (pinfunction "2_2") (pintype "passive"))
      (node (ref "U3") (pin "8") (pinfunction "BOLX_8") (pintype "passive"))
    )
    (net (code "53") (name "Net-(U3-BULX)") (class "Default")
      (node (ref "L1") (pin "1") (pinfunction "1_1") (pintype "passive"))
      (node (ref "U3") (pin "11") (pinfunction "BULX_11") (pintype "passive"))
    )
    (net (code "54") (name "VDD_MCU") (class "Default")
      (node (ref "C2") (pin "2") (pinfunction "2_2") (pintype "passive"))
      (node (ref "C3") (pin "2") (pinfunction "2_2") (pintype "passive"))
      (node (ref "C5") (pin "2") (pinfunction "2_2") (pintype "passive"))
      (node (ref "SB1") (pin "1") (pinfunction "C1_1") (pintype "passive"))
      (node (ref "SB2") (pin "2") (pinfunction "C2_2") (pintype "passive"))
      (node (ref "U2") (pin "4") (pinfunction "VDD_USB_4") (pintype "power_in"))
      (node (ref "U2") (pin "5") (pinfunction "VDD_MCU_5") (pintype "power_in"))
    )
    (net (code "55") (name "VDD_RF") (class "Default")
      (node (ref "C4") (pin "2") (pinfunction "2_2") (pintype "passive"))
      (node (ref "C6") (pin "2") (pinfunction "2_2") (pintype "passive"))
      (node (ref "SB3") (pin "2") (pinfunction "C2_2") (pintype "passive"))
      (node (ref "U2") (pin "6") (pinfunction "VDD_RF_6") (pintype "power_in"))
    )
    (net (code "56") (name "unconnected-(P2-PadMP1)") (class "Default")
      (node (ref "P2") (pin "MP1") (pinfunction "MP1_MP1") (pintype "passive+no_connect"))
    )
    (net (code "57") (name "unconnected-(P2-PadMP2)") (class "Default")
      (node (ref "P2") (pin "MP2") (pinfunction "MP2_MP2") (pintype "passive+no_connect"))
    )
    (net (code "58") (name "unconnected-(P5-Pad6)") (class "Default")
      (node (ref "P5") (pin "6") (pinfunction "6_6") (pintype "passive+no_connect"))
    )
    (net (code "59") (name "unconnected-(P5-Pad7)") (class "Default")
      (node (ref "P5") (pin "7") (pinfunction "7_7") (pintype "passive+no_connect"))
    )
    (net (code "60") (name "unconnected-(P5-Pad8)") (class "Default")
      (node (ref "P5") (pin "8") (pinfunction "8_8") (pintype "passive+no_connect"))
    )
    (net (code "61") (name "unconnected-(U1-NC-Pad4)") (class "Default")
      (node (ref "U1") (pin "4") (pinfunction "NC_4") (pintype "passive+no_connect"))
    )
  )
)
